# Charger.net
KiCad netlist of a schematic drawn in Altium Designer
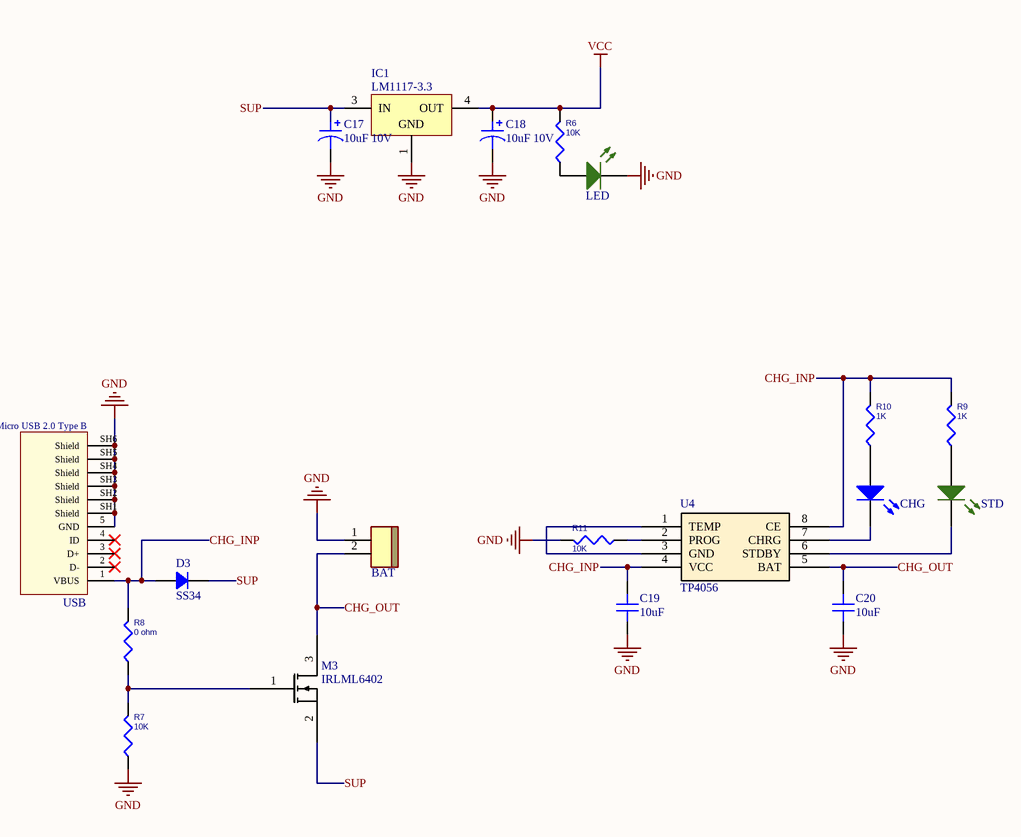
[diagram p0: Charger.SchDoc]

(export (version "E")
  (design (tool "Eeschema 10.0.6"))
  (components
    (comp (ref "BAT")
      (value "JST BxB-PH-K 2Pin")
      (footprint "JST B2B-PH-K")
      (description "Connector Header Through Hole 0.079\" (2.00mm)")
      (fields (field (name "PARTNUMBER") "B2B-PH-K-S(LF)(SN)"))
      (libsource (lib "Conn Terminal") (part "JST BxB-PH-K 2Pin"))
    )
    (comp (ref "C17")
      (value "10uF 10V")
      (footprint "CAP TANSMD 1206_3216 CASE A")
      (description "SMT Tantalum Capacitor")
      (libsource (lib "Capacitor") (part "Cap Tan Case A"))
    )
    (comp (ref "C18")
      (value "10uF 10V")
      (footprint "CAP TANSMD 1206_3216 CASE A")
      (description "SMT Tantalum Capacitor")
      (libsource (lib "Capacitor") (part "Cap Tan Case A"))
    )
    (comp (ref "C19")
      (value "10uF")
      (footprint "CAP 0603_1608")
      (description "SMT Capacitor")
      (libsource (lib "Capacitor") (part "Cap 0603"))
    )
    (comp (ref "C20")
      (value "10uF")
      (footprint "CAP 0603_1608")
      (description "SMT Capacitor")
      (libsource (lib "Capacitor") (part "Cap 0603"))
    )
    (comp (ref "CHG")
      (value "LED SMD 0603 BLUE")
      (footprint "LED_0603_RED")
      (libsource (lib "Led") (part "LED SMD 0603 BLUE"))
    )
    (comp (ref "D3")
      (value "SS34")
      (footprint "DO-214AC SMA")
      (description "Diode Standard 1000V 1A Surface Mount SMA")
      (libsource (lib "Diode") (part "US1M (SMD SMA)"))
    )
    (comp (ref "IC1")
      (value "LM1117-3.3")
      (footprint "TD03B_N")
      (description "x.x Volt, 800mA Low-Dropout Linear Regulator, 3-pin TO-252")
      (fields
        (field (name "PARTNUMBER") "LM1117DT-3.3")
        (field (name "MANUFACTURER") "National Semiconductor")
      )
      (libsource (lib "My_Library") (part "LM1117DT-x.x"))
    )
    (comp (ref "LED")
      (value "LED SMD 0603 GREEN")
      (footprint "LED_0603_GREEN")
      (libsource (lib "Led") (part "LED SMD 0603 GREEN"))
    )
    (comp (ref "M3") (value "IRLML6402") (footprint "SOT-23") (libsource (lib "Salman_lib") (part "2N7002A")))
    (comp (ref "R6") (value "10K") (footprint "0603R") (libsource (lib "NAHAL_LIB") (part "R")))
    (comp (ref "R7") (value "10K") (footprint "0603R") (libsource (lib "NAHAL_LIB") (part "R")))
    (comp (ref "R8") (value "0 ohm") (footprint "0603R") (libsource (lib "NAHAL_LIB") (part "R")))
    (comp (ref "R9") (value "1K") (footprint "0603R") (libsource (lib "NAHAL_LIB") (part "R")))
    (comp (ref "R10") (value "1K") (footprint "0603R") (libsource (lib "NAHAL_LIB") (part "R")))
    (comp (ref "R11") (value "10K") (footprint "0603R") (libsource (lib "NAHAL_LIB") (part "R")))
    (comp (ref "STD")
      (value "LED SMD 0603 GREEN")
      (footprint "LED_0603_GREEN")
      (libsource (lib "Led") (part "LED SMD 0603 GREEN"))
    )
    (comp (ref "U4") (value "TP4056") (footprint "SOIC-8") (libsource (lib "Salman_lib") (part "TP4056")))
    (comp (ref "USB")
      (value "Micro USB 2.0 Type B")
      (footprint "USB_MICRO_B_BM_SHT")
      (description "USB - micro B  Receptacle Connector 5 Position Surface Mount, Right Angle")
      (fields (field (name "PARTNUMBER") "UB-MC5BR3-SD204-4S-1-TB NMP"))
      (libsource (lib "Conn Usb") (part "Micro USB 2.0 Type B Horizonta (SMD) UB-MC5BR3-SD204-4S-1-TB NMP"))
    )
  )
  (nets
    (net (code "1") (name "/CHG_INP") (class "Default")
      (node (ref "C19") (pin "1") (pinfunction "1_1") (pintype "passive"))
      (node (ref "D3") (pin "1") (pinfunction "1_1") (pintype "passive"))
      (node (ref "R10") (pin "2") (pinfunction "2_2") (pintype "passive"))
      (node (ref "R8") (pin "2") (pinfunction "2_2") (pintype "passive"))
      (node (ref "R9") (pin "2") (pinfunction "2_2") (pintype "passive"))
      (node (ref "U4") (pin "4") (pinfunction "VCC_4") (pintype "passive"))
      (node (ref "U4") (pin "8") (pinfunction "CE_8") (pintype "passive"))
      (node (ref "USB") (pin "1") (pinfunction "VBUS_1") (pintype "passive"))
    )
    (net (code "2") (name "/CHG_OUT") (class "Default")
      (node (ref "BAT") (pin "2") (pinfunction "2_2") (pintype "passive"))
      (node (ref "C20") (pin "1") (pinfunction "1_1") (pintype "passive"))
      (node (ref "M3") (pin "3") (pintype "passive"))
      (node (ref "U4") (pin "5") (pinfunction "BAT_5") (pintype "passive"))
    )
    (net (code "3") (name "/SUP") (class "Default")
      (node (ref "C17") (pin "1") (pinfunction "1_1") (pintype "passive"))
      (node (ref "D3") (pin "2") (pinfunction "2_2") (pintype "passive"))
      (node (ref "IC1") (pin "3") (pinfunction "IN_3") (pintype "power_in"))
      (node (ref "M3") (pin "2") (pintype "passive"))
    )
    (net (code "4") (name "GND") (class "Default")
      (node (ref "BAT") (pin "1") (pinfunction "1_1") (pintype "passive"))
      (node (ref "C17") (pin "2") (pinfunction "2_2") (pintype "passive"))
      (node (ref "C18") (pin "2") (pinfunction "2_2") (pintype "passive"))
      (node (ref "C19") (pin "2") (pinfunction "2_2") (pintype "passive"))
      (node (ref "C20") (pin "2") (pinfunction "2_2") (pintype "passive"))
      (node (ref "IC1") (pin "1") (pinfunction "GND_1") (pintype "power_in"))
      (node (ref "LED") (pin "2") (pinfunction "K_2") (pintype "passive"))
      (node (ref "R11") (pin "2") (pinfunction "2_2") (pintype "passive"))
      (node (ref "R7") (pin "1") (pinfunction "1_1") (pintype "passive"))
      (node (ref "USB") (pin "5") (pinfunction "GND_5") (pintype "passive"))
      (node (ref "USB") (pin "SH1") (pinfunction "Shield_SH1") (pintype "passive"))
      (node (ref "USB") (pin "SH2") (pinfunction "Shield_SH2") (pintype "passive"))
      (node (ref "USB") (pin "SH3") (pinfunction "Shield_SH3") (pintype "passive"))
      (node (ref "USB") (pin "SH4") (pinfunction "Shield_SH4") (pintype "passive"))
      (node (ref "USB") (pin "SH5") (pinfunction "Shield_SH5") (pintype "passive"))
      (node (ref "USB") (pin "SH6") (pinfunction "Shield_SH6") (pintype "passive"))
    )
    (net (code "5") (name "Net-(CHG-A)") (class "Default")
      (node (ref "CHG") (pin "1") (pinfunction "A_1") (pintype "passive"))
      (node (ref "R10") (pin "1") (pinfunction "1_1") (pintype "passive"))
    )
    (net (code "6") (name "Net-(CHG-K)") (class "Default")
      (node (ref "CHG") (pin "2") (pinfunction "K_2") (pintype "passive"))
      (node (ref "U4") (pin "7") (pinfunction "CHRG_7") (pintype "passive"))
    )
    (net (code "7") (name "Net-(LED-A)") (class "Default")
      (node (ref "LED") (pin "1") (pinfunction "A_1") (pintype "passive"))
      (node (ref "R6") (pin "1") (pinfunction "1_1") (pintype "passive"))
    )
    (net (code "8") (name "Net-(M3-Pad1)") (class "Default")
      (node (ref "M3") (pin "1") (pintype "passive"))
      (node (ref "R7") (pin "2") (pinfunction "2_2") (pintype "passive"))
      (node (ref "R8") (pin "1") (pinfunction "1_1") (pintype "passive"))
    )
    (net (code "9") (name "Net-(STD-A)") (class "Default")
      (node (ref "R9") (pin "1") (pinfunction "1_1") (pintype "passive"))
      (node (ref "STD") (pin "1") (pinfunction "A_1") (pintype "passive"))
    )
    (net (code "10") (name "Net-(STD-K)") (class "Default")
      (node (ref "STD") (pin "2") (pinfunction "K_2") (pintype "passive"))
      (node (ref "U4") (pin "6") (pinfunction "STDBY_6") (pintype "passive"))
    )
    (net (code "11") (name "Net-(U4-GND)") (class "Default")
      (node (ref "U4") (pin "1") (pinfunction "TEMP_1") (pintype "passive"))
      (node (ref "U4") (pin "3") (pinfunction "GND_3") (pintype "passive"))
    )
    (net (code "12") (name "Net-(U4-PROG)") (class "Default")
      (node (ref "R11") (pin "1") (pinfunction "1_1") (pintype "passive"))
      (node (ref "U4") (pin "2") (pinfunction "PROG_2") (pintype "passive"))
    )
    (net (code "13") (name "VCC") (class "Default")
      (node (ref "C18") (pin "1") (pinfunction "1_1") (pintype "passive"))
      (node (ref "IC1") (pin "4") (pinfunction "OUT_4") (pintype "power_in"))
      (node (ref "R6") (pin "2") (pinfunction "2_2") (pintype "passive"))
    )
    (net (code "14") (name "unconnected-(USB-D+-Pad3)") (class "Default")
      (node (ref "USB") (pin "3") (pinfunction "D+_3") (pintype "passive+no_connect"))
    )
    (net (code "15") (name "unconnected-(USB-D--Pad2)") (class "Default")
      (node (ref "USB") (pin "2") (pinfunction "D-_2") (pintype "passive+no_connect"))
    )
    (net (code "16") (name "unconnected-(USB-ID-Pad4)") (class "Default")
      (node (ref "USB") (pin "4") (pinfunction "ID_4") (pintype "passive+no_connect"))
    )
  )
)
